# Encoder.net
KiCad netlist of a schematic drawn in Altium Designer
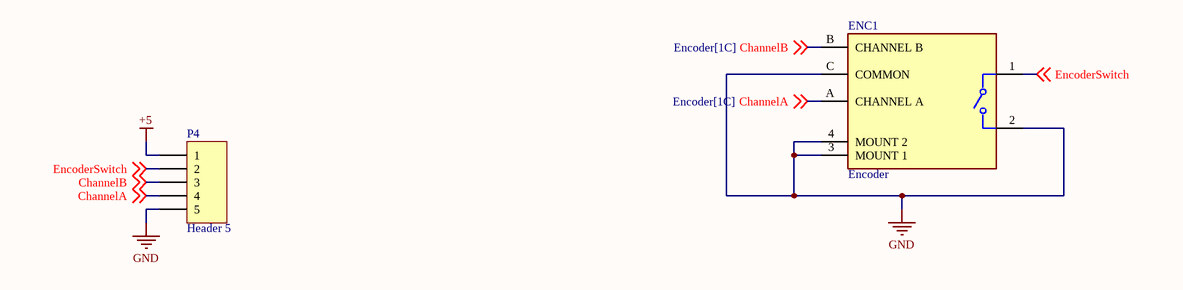
[diagram p0: Encoder.SchDoc]

(export (version "E")
  (design (tool "Eeschema 10.0.6"))
  (components
    (comp (ref "ENC1")
      (value "Encoder")
      (footprint "FP-PEC12R-4117F-S0012-0")
      (libsource (lib "Soldeerstation") (part "Encoder"))
    )
    (comp (ref "P4")
      (value "Header 5")
      (footprint "HDR1X5")
      (description "Header, 5-Pin")
      (fields (field (name "PUBLISHER") "Altium Limited"))
      (libsource (lib "Miscellaneous Connectors") (part "Header 5"))
    )
  )
  (nets
    (net (code "1") (name "+5") (class "Default")
      (node (ref "P4") (pin "1") (pinfunction "1_1") (pintype "passive"))
    )
    (net (code "2") (name "ChannelA") (class "Default")
      (node (ref "ENC1") (pin "A") (pinfunction "CHANNEL_A_A") (pintype "passive"))
      (node (ref "P4") (pin "4") (pinfunction "4_4") (pintype "passive"))
    )
    (net (code "3") (name "ChannelB") (class "Default")
      (node (ref "ENC1") (pin "B") (pinfunction "CHANNEL_B_B") (pintype "passive"))
      (node (ref "P4") (pin "3") (pinfunction "3_3") (pintype "passive"))
    )
    (net (code "4") (name "EncoderSwitch") (class "Default")
      (node (ref "ENC1") (pin "1") (pinfunction "1_1") (pintype "passive"))
      (node (ref "P4") (pin "2") (pinfunction "2_2") (pintype "passive"))
    )
    (net (code "5") (name "GND") (class "Default")
      (node (ref "ENC1") (pin "2") (pinfunction "2_2") (pintype "passive"))
      (node (ref "ENC1") (pin "3") (pinfunction "MOUNT_1_3") (pintype "passive"))
      (node (ref "ENC1") (pin "4") (pinfunction "MOUNT_2_4") (pintype "passive"))
      (node (ref "ENC1") (pin "C") (pinfunction "COMMON_C") (pintype "passive"))
      (node (ref "P4") (pin "5") (pinfunction "5_5") (pintype "passive"))
    )
  )
)
